# BMS_SafetyCircuit.net
KiCad netlist of a schematic drawn in Altium Designer
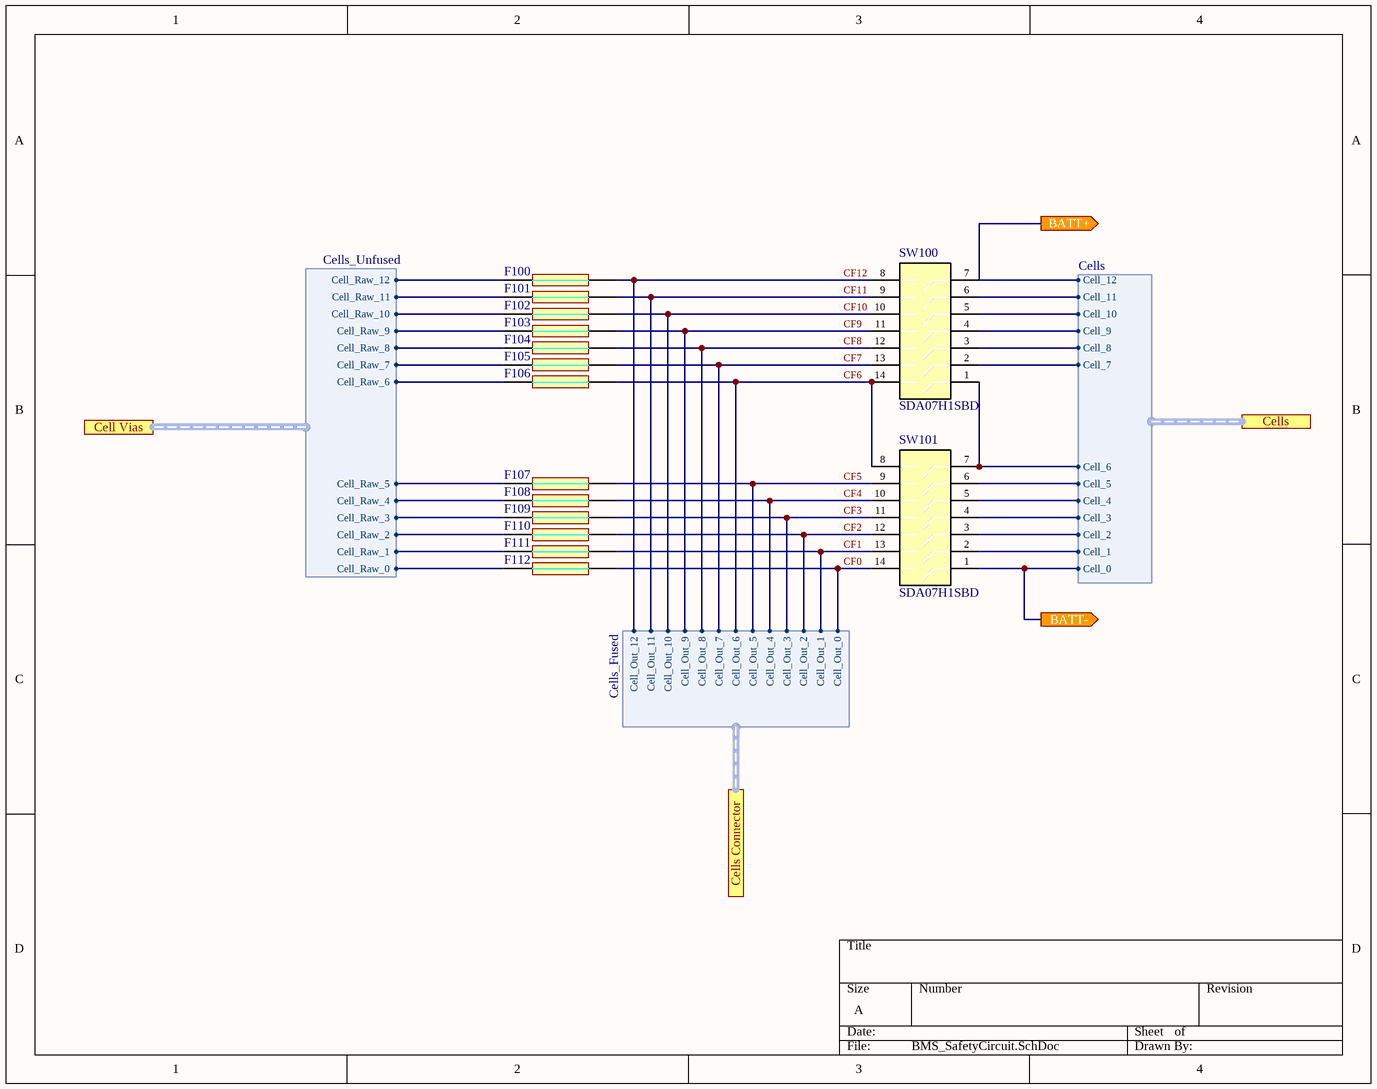
[diagram p0: BMS_SafetyCircuit.SchDoc]

(export (version "E")
  (design (tool "Eeschema 10.0.6"))
  (components
    (comp (ref "F100")
      (value "SFP200F")
      (footprint "DIOC3216X12N")
      (description "Surface Mount Fuses VERY FAST GLASS CER 63V 2A SZ 1206")
      (libsource (lib "SFP200F") (part "SFP200F"))
    )
    (comp (ref "F101")
      (value "SFP200F")
      (footprint "DIOC3216X12N")
      (description "Surface Mount Fuses VERY FAST GLASS CER 63V 2A SZ 1206")
      (libsource (lib "SFP200F") (part "SFP200F"))
    )
    (comp (ref "F102")
      (value "SFP200F")
      (footprint "DIOC3216X12N")
      (description "Surface Mount Fuses VERY FAST GLASS CER 63V 2A SZ 1206")
      (libsource (lib "SFP200F") (part "SFP200F"))
    )
    (comp (ref "F103")
      (value "SFP200F")
      (footprint "DIOC3216X12N")
      (description "Surface Mount Fuses VERY FAST GLASS CER 63V 2A SZ 1206")
      (libsource (lib "SFP200F") (part "SFP200F"))
    )
    (comp (ref "F104")
      (value "SFP200F")
      (footprint "DIOC3216X12N")
      (description "Surface Mount Fuses VERY FAST GLASS CER 63V 2A SZ 1206")
      (libsource (lib "SFP200F") (part "SFP200F"))
    )
    (comp (ref "F105")
      (value "SFP200F")
      (footprint "DIOC3216X12N")
      (description "Surface Mount Fuses VERY FAST GLASS CER 63V 2A SZ 1206")
      (libsource (lib "SFP200F") (part "SFP200F"))
    )
    (comp (ref "F106")
      (value "SFP200F")
      (footprint "DIOC3216X12N")
      (description "Surface Mount Fuses VERY FAST GLASS CER 63V 2A SZ 1206")
      (libsource (lib "SFP200F") (part "SFP200F"))
    )
    (comp (ref "F107")
      (value "SFP200F")
      (footprint "DIOC3216X12N")
      (description "Surface Mount Fuses VERY FAST GLASS CER 63V 2A SZ 1206")
      (libsource (lib "SFP200F") (part "SFP200F"))
    )
    (comp (ref "F108")
      (value "SFP200F")
      (footprint "DIOC3216X12N")
      (description "Surface Mount Fuses VERY FAST GLASS CER 63V 2A SZ 1206")
      (libsource (lib "SFP200F") (part "SFP200F"))
    )
    (comp (ref "F109")
      (value "SFP200F")
      (footprint "DIOC3216X12N")
      (description "Surface Mount Fuses VERY FAST GLASS CER 63V 2A SZ 1206")
      (libsource (lib "SFP200F") (part "SFP200F"))
    )
    (comp (ref "F110")
      (value "SFP200F")
      (footprint "DIOC3216X12N")
      (description "Surface Mount Fuses VERY FAST GLASS CER 63V 2A SZ 1206")
      (libsource (lib "SFP200F") (part "SFP200F"))
    )
    (comp (ref "F111")
      (value "SFP200F")
      (footprint "DIOC3216X12N")
      (description "Surface Mount Fuses VERY FAST GLASS CER 63V 2A SZ 1206")
      (libsource (lib "SFP200F") (part "SFP200F"))
    )
    (comp (ref "F112")
      (value "SFP200F")
      (footprint "DIOC3216X12N")
      (description "Surface Mount Fuses VERY FAST GLASS CER 63V 2A SZ 1206")
      (libsource (lib "SFP200F") (part "SFP200F"))
    )
    (comp (ref "SW100")
      (value "SDA07H1SBD")
      (footprint "7 pos Dip-Switch")
      (description "Dip Switch SPST 7 Position Surface Mount Slide (Standard) Actuator 25mA 24VDC")
      (libsource (lib "SDA07H1SBD") (part "Dip Switches"))
    )
    (comp (ref "SW101")
      (value "SDA07H1SBD")
      (footprint "7 pos Dip-Switch")
      (description "Dip Switch SPST 7 Position Surface Mount Slide (Standard) Actuator 25mA 24VDC")
      (libsource (lib "SDA07H1SBD") (part "Dip Switches"))
    )
  )
  (nets
    (net (code "4") (name "/BATT+") (class "Default")
      (node (ref "SW100") (pin "7") (pinfunction "7_7") (pintype "passive"))
    )
    (net (code "5") (name "/BATT-") (class "Default")
      (node (ref "SW101") (pin "1") (pinfunction "1_1") (pintype "passive"))
    )
    (net (code "6") (name "/CF0") (class "Default")
      (node (ref "F112") (pin "2") (pinfunction "2_2") (pintype "passive"))
      (node (ref "SW101") (pin "14") (pinfunction "14_14") (pintype "passive"))
    )
    (net (code "7") (name "/CF1") (class "Default")
      (node (ref "F111") (pin "2") (pinfunction "2_2") (pintype "passive"))
      (node (ref "SW101") (pin "13") (pinfunction "13_13") (pintype "passive"))
    )
    (net (code "8") (name "/CF2") (class "Default")
      (node (ref "F110") (pin "2") (pinfunction "2_2") (pintype "passive"))
      (node (ref "SW101") (pin "12") (pinfunction "12_12") (pintype "passive"))
    )
    (net (code "9") (name "/CF3") (class "Default")
      (node (ref "F109") (pin "2") (pinfunction "2_2") (pintype "passive"))
      (node (ref "SW101") (pin "11") (pinfunction "11_11") (pintype "passive"))
    )
    (net (code "10") (name "/CF4") (class "Default")
      (node (ref "F108") (pin "2") (pinfunction "2_2") (pintype "passive"))
      (node (ref "SW101") (pin "10") (pinfunction "10_10") (pintype "passive"))
    )
    (net (code "11") (name "/CF5") (class "Default")
      (node (ref "F107") (pin "2") (pinfunction "2_2") (pintype "passive"))
      (node (ref "SW101") (pin "9") (pinfunction "9_9") (pintype "passive"))
    )
    (net (code "12") (name "/CF6") (class "Default")
      (node (ref "F106") (pin "2") (pinfunction "2_2") (pintype "passive"))
      (node (ref "SW100") (pin "14") (pinfunction "14_14") (pintype "passive"))
      (node (ref "SW101") (pin "8") (pinfunction "8_8") (pintype "passive"))
    )
    (net (code "13") (name "/CF7") (class "Default")
      (node (ref "F105") (pin "2") (pinfunction "2_2") (pintype "passive"))
      (node (ref "SW100") (pin "13") (pinfunction "13_13") (pintype "passive"))
    )
    (net (code "14") (name "/CF8") (class "Default")
      (node (ref "F104") (pin "2") (pinfunction "2_2") (pintype "passive"))
      (node (ref "SW100") (pin "12") (pinfunction "12_12") (pintype "passive"))
    )
    (net (code "15") (name "/CF9") (class "Default")
      (node (ref "F103") (pin "2") (pinfunction "2_2") (pintype "passive"))
      (node (ref "SW100") (pin "11") (pinfunction "11_11") (pintype "passive"))
    )
    (net (code "16") (name "/CF10") (class "Default")
      (node (ref "F102") (pin "2") (pinfunction "2_2") (pintype "passive"))
      (node (ref "SW100") (pin "10") (pinfunction "10_10") (pintype "passive"))
    )
    (net (code "17") (name "/CF11") (class "Default")
      (node (ref "F101") (pin "2") (pinfunction "2_2") (pintype "passive"))
      (node (ref "SW100") (pin "9") (pinfunction "9_9") (pintype "passive"))
    )
    (net (code "18") (name "/CF12") (class "Default")
      (node (ref "F100") (pin "2") (pinfunction "2_2") (pintype "passive"))
      (node (ref "SW100") (pin "8") (pinfunction "8_8") (pintype "passive"))
    )
    (net (code "19") (name "/Cell_1") (class "Default")
      (node (ref "SW101") (pin "2") (pinfunction "2_2") (pintype "passive"))
    )
    (net (code "20") (name "/Cell_2") (class "Default")
      (node (ref "SW101") (pin "3") (pinfunction "3_3") (pintype "passive"))
    )
    (net (code "21") (name "/Cell_3") (class "Default")
      (node (ref "SW101") (pin "4") (pinfunction "4_4") (pintype "passive"))
    )
    (net (code "22") (name "/Cell_4") (class "Default")
      (node (ref "SW101") (pin "5") (pinfunction "5_5") (pintype "passive"))
    )
    (net (code "23") (name "/Cell_5") (class "Default")
      (node (ref "SW101") (pin "6") (pinfunction "6_6") (pintype "passive"))
    )
    (net (code "24") (name "/Cell_6") (class "Default")
      (node (ref "SW100") (pin "1") (pinfunction "1_1") (pintype "passive"))
      (node (ref "SW101") (pin "7") (pinfunction "7_7") (pintype "passive"))
    )
    (net (code "25") (name "/Cell_7") (class "Default")
      (node (ref "SW100") (pin "2") (pinfunction "2_2") (pintype "passive"))
    )
    (net (code "26") (name "/Cell_8") (class "Default")
      (node (ref "SW100") (pin "3") (pinfunction "3_3") (pintype "passive"))
    )
    (net (code "27") (name "/Cell_9") (class "Default")
      (node (ref "SW100") (pin "4") (pinfunction "4_4") (pintype "passive"))
    )
    (net (code "28") (name "/Cell_10") (class "Default")
      (node (ref "SW100") (pin "5") (pinfunction "5_5") (pintype "passive"))
    )
    (net (code "29") (name "/Cell_11") (class "Default")
      (node (ref "SW100") (pin "6") (pinfunction "6_6") (pintype "passive"))
    )
    (net (code "30") (name "/Cell_Raw_0") (class "Default")
      (node (ref "F112") (pin "1") (pinfunction "1_1") (pintype "passive"))
    )
    (net (code "31") (name "/Cell_Raw_1") (class "Default")
      (node (ref "F111") (pin "1") (pinfunction "1_1") (pintype "passive"))
    )
    (net (code "32") (name "/Cell_Raw_2") (class "Default")
      (node (ref "F110") (pin "1") (pinfunction "1_1") (pintype "passive"))
    )
    (net (code "33") (name "/Cell_Raw_3") (class "Default")
      (node (ref "F109") (pin "1") (pinfunction "1_1") (pintype "passive"))
    )
    (net (code "34") (name "/Cell_Raw_4") (class "Default")
      (node (ref "F108") (pin "1") (pinfunction "1_1") (pintype "passive"))
    )
    (net (code "35") (name "/Cell_Raw_5") (class "Default")
      (node (ref "F107") (pin "1") (pinfunction "1_1") (pintype "passive"))
    )
    (net (code "36") (name "/Cell_Raw_6") (class "Default")
      (node (ref "F106") (pin "1") (pinfunction "1_1") (pintype "passive"))
    )
    (net (code "37") (name "/Cell_Raw_7") (class "Default")
      (node (ref "F105") (pin "1") (pinfunction "1_1") (pintype "passive"))
    )
    (net (code "38") (name "/Cell_Raw_8") (class "Default")
      (node (ref "F104") (pin "1") (pinfunction "1_1") (pintype "passive"))
    )
    (net (code "39") (name "/Cell_Raw_9") (class "Default")
      (node (ref "F103") (pin "1") (pinfunction "1_1") (pintype "passive"))
    )
    (net (code "40") (name "/Cell_Raw_10") (class "Default")
      (node (ref "F102") (pin "1") (pinfunction "1_1") (pintype "passive"))
    )
    (net (code "41") (name "/Cell_Raw_11") (class "Default")
      (node (ref "F101") (pin "1") (pinfunction "1_1") (pintype "passive"))
    )
    (net (code "42") (name "/Cell_Raw_12") (class "Default")
      (node (ref "F100") (pin "1") (pinfunction "1_1") (pintype "passive"))
    )
  )
)
